# redmaus-ir-tx-amp-mk-1_2.net
KiCad netlist of a schematic drawn in EAGLE
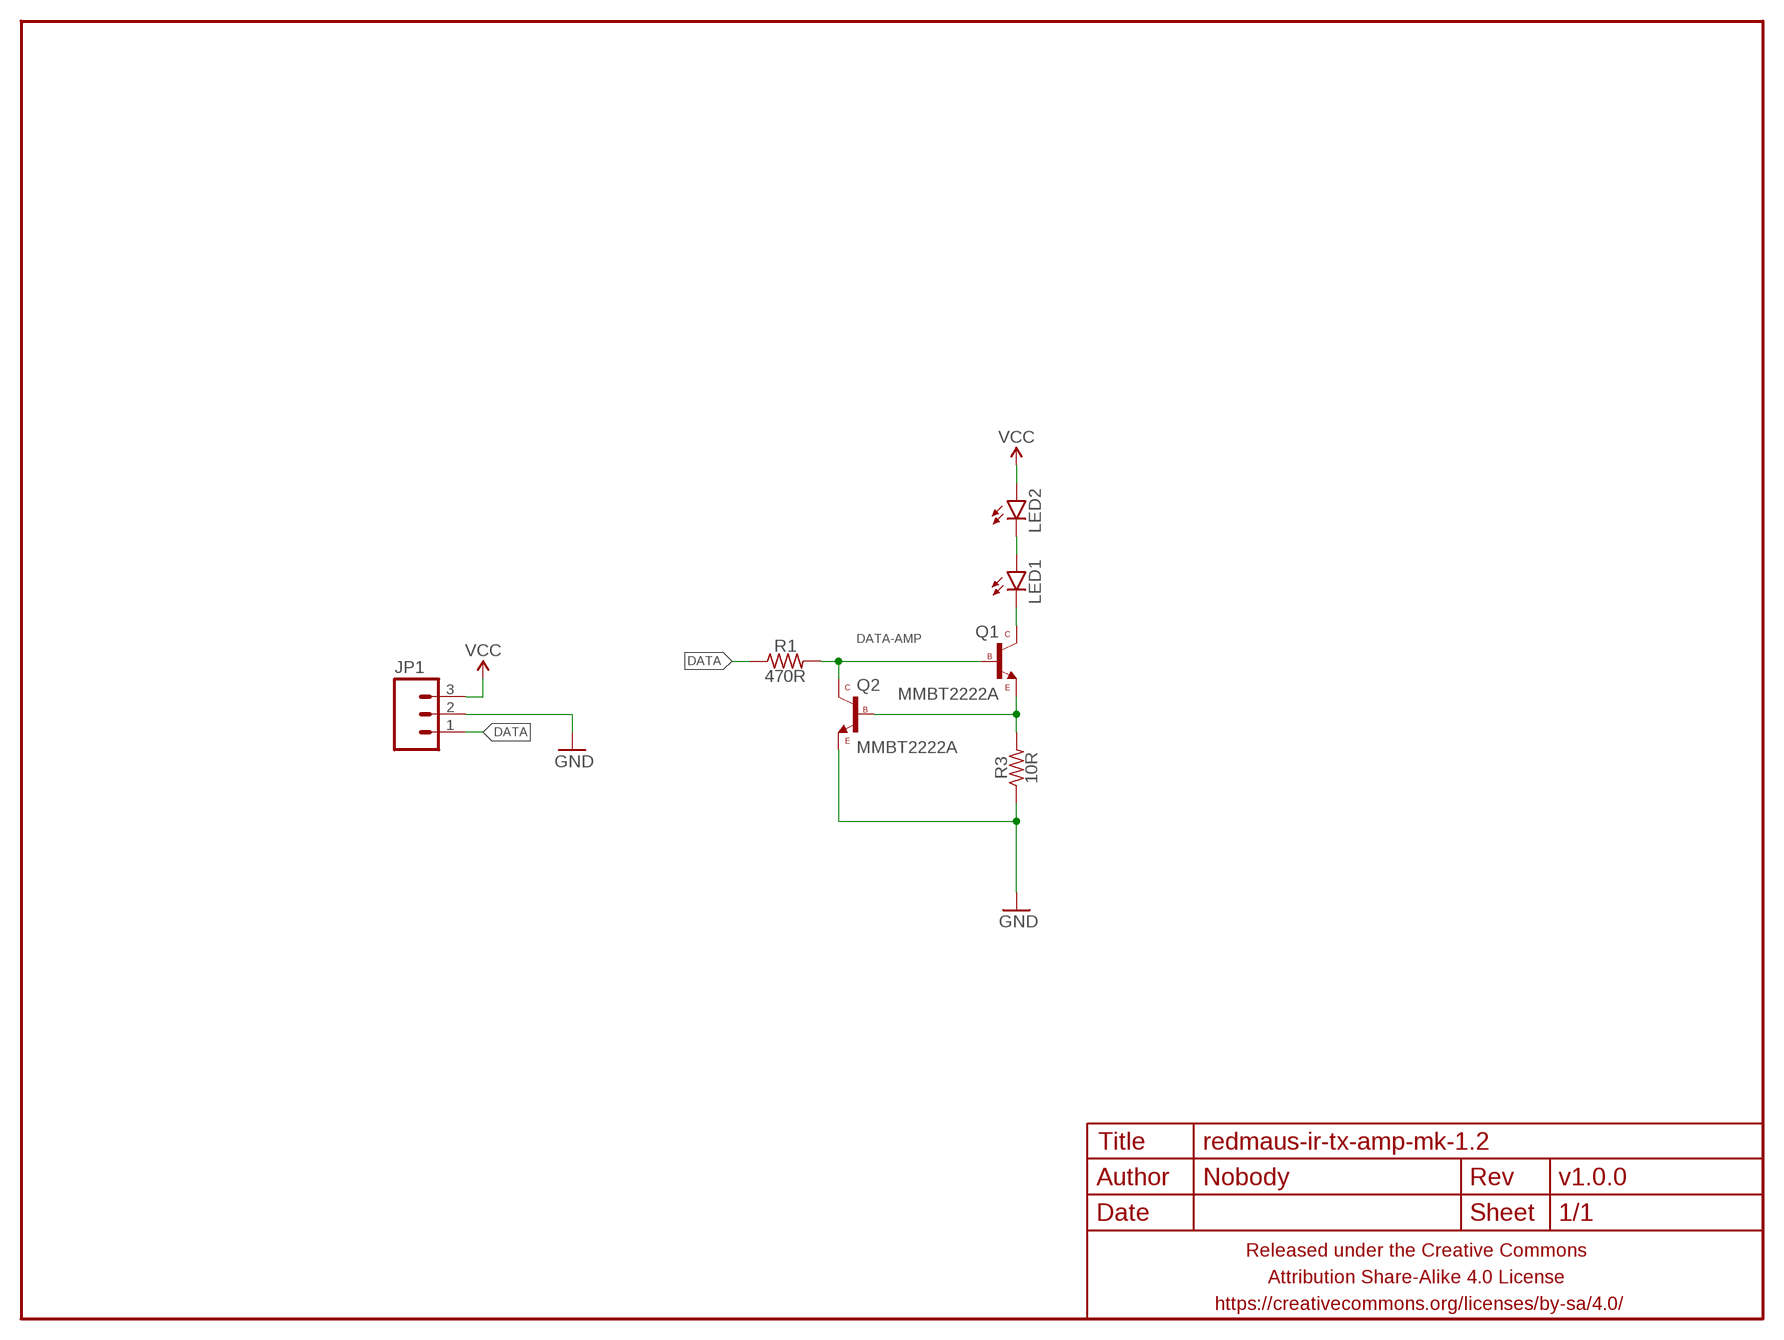
[diagram p0: schematic, sheet 1]

(export (version "E")
  (design (tool "Eeschema 10.0.6"))
  (components
    (comp (ref "FRAME1")
      (value "FRAME-LETTERNO_PACKAGE")
      (footprint "eagle-import:DUMMY")
      (fields (field (name "VERSION") "v1.0.0") (field (name "DESIGNER") "Nobody"))
      (libsource (lib "eagle-import") (part "FRAME-LETTERNO_PACKAGE"))
    )
    (comp (ref "JP1")
      (value "M03PTH-CENTERED")
      (footprint "eagle-import:1X03-CENTERED")
      (libsource (lib "eagle-import") (part "M03PTH-CENTERED"))
    )
    (comp (ref "LED1")
      (value "LED5MM_SHORTPADS")
      (footprint "eagle-import:LED5MM_SHORTPADS")
      (libsource (lib "eagle-import") (part "LED5MM_SHORTPADS"))
    )
    (comp (ref "LED2")
      (value "LED5MM_SHORTPADS")
      (footprint "eagle-import:LED5MM_SHORTPADS")
      (libsource (lib "eagle-import") (part "LED5MM_SHORTPADS"))
    )
    (comp (ref "Q1")
      (value "MMBT2222A")
      (footprint "eagle-import:SOT23")
      (libsource (lib "eagle-import") (part "TRANSISTOR_NPNMMBT2222A"))
    )
    (comp (ref "Q2")
      (value "MMBT2222A")
      (footprint "eagle-import:SOT23")
      (libsource (lib "eagle-import") (part "TRANSISTOR_NPNMMBT2222A"))
    )
    (comp (ref "R1")
      (value "470R")
      (footprint "eagle-import:R0603-TIGHTER")
      (libsource (lib "eagle-import") (part "RESISTORR0603-TIGHTER"))
    )
    (comp (ref "R3")
      (value "10R")
      (footprint "eagle-import:R0603-TIGHTER")
      (libsource (lib "eagle-import") (part "RESISTORR0603-TIGHTER"))
    )
  )
  (nets
    (net (code "1") (name "/DATA-AMP") (class "Default")
      (node (ref "Q1") (pin "1") (pinfunction "B_1") (pintype "passive"))
      (node (ref "Q2") (pin "3") (pinfunction "C_3") (pintype "passive"))
      (node (ref "R1") (pin "2") (pinfunction "2_2") (pintype "passive"))
    )
    (net (code "2") (name "DATA") (class "Default")
      (node (ref "JP1") (pin "1") (pinfunction "1_1") (pintype "passive"))
      (node (ref "R1") (pin "1") (pinfunction "1_1") (pintype "passive"))
    )
    (net (code "3") (name "GND") (class "Default")
      (node (ref "JP1") (pin "2") (pinfunction "2_2") (pintype "passive"))
      (node (ref "Q2") (pin "2") (pinfunction "E_2") (pintype "passive"))
      (node (ref "R3") (pin "1") (pinfunction "1_1") (pintype "passive"))
    )
    (net (code "4") (name "Net-(LED1-C)") (class "Default")
      (node (ref "LED1") (pin "K") (pinfunction "C_K") (pintype "passive"))
      (node (ref "Q1") (pin "3") (pinfunction "C_3") (pintype "passive"))
    )
    (net (code "5") (name "Net-(LED2-C)") (class "Default")
      (node (ref "LED1") (pin "A") (pinfunction "A_A") (pintype "passive"))
      (node (ref "LED2") (pin "K") (pinfunction "C_K") (pintype "passive"))
    )
    (net (code "6") (name "Net-(Q1-E)") (class "Default")
      (node (ref "Q1") (pin "2") (pinfunction "E_2") (pintype "passive"))
      (node (ref "Q2") (pin "1") (pinfunction "B_1") (pintype "passive"))
      (node (ref "R3") (pin "2") (pinfunction "2_2") (pintype "passive"))
    )
    (net (code "7") (name "VCC") (class "Default")
      (node (ref "JP1") (pin "3") (pinfunction "3_3") (pintype "passive"))
      (node (ref "LED2") (pin "A") (pinfunction "A_A") (pintype "passive"))
    )
  )
)
